# impulse.net
KiCad netlist of a schematic drawn in EAGLE
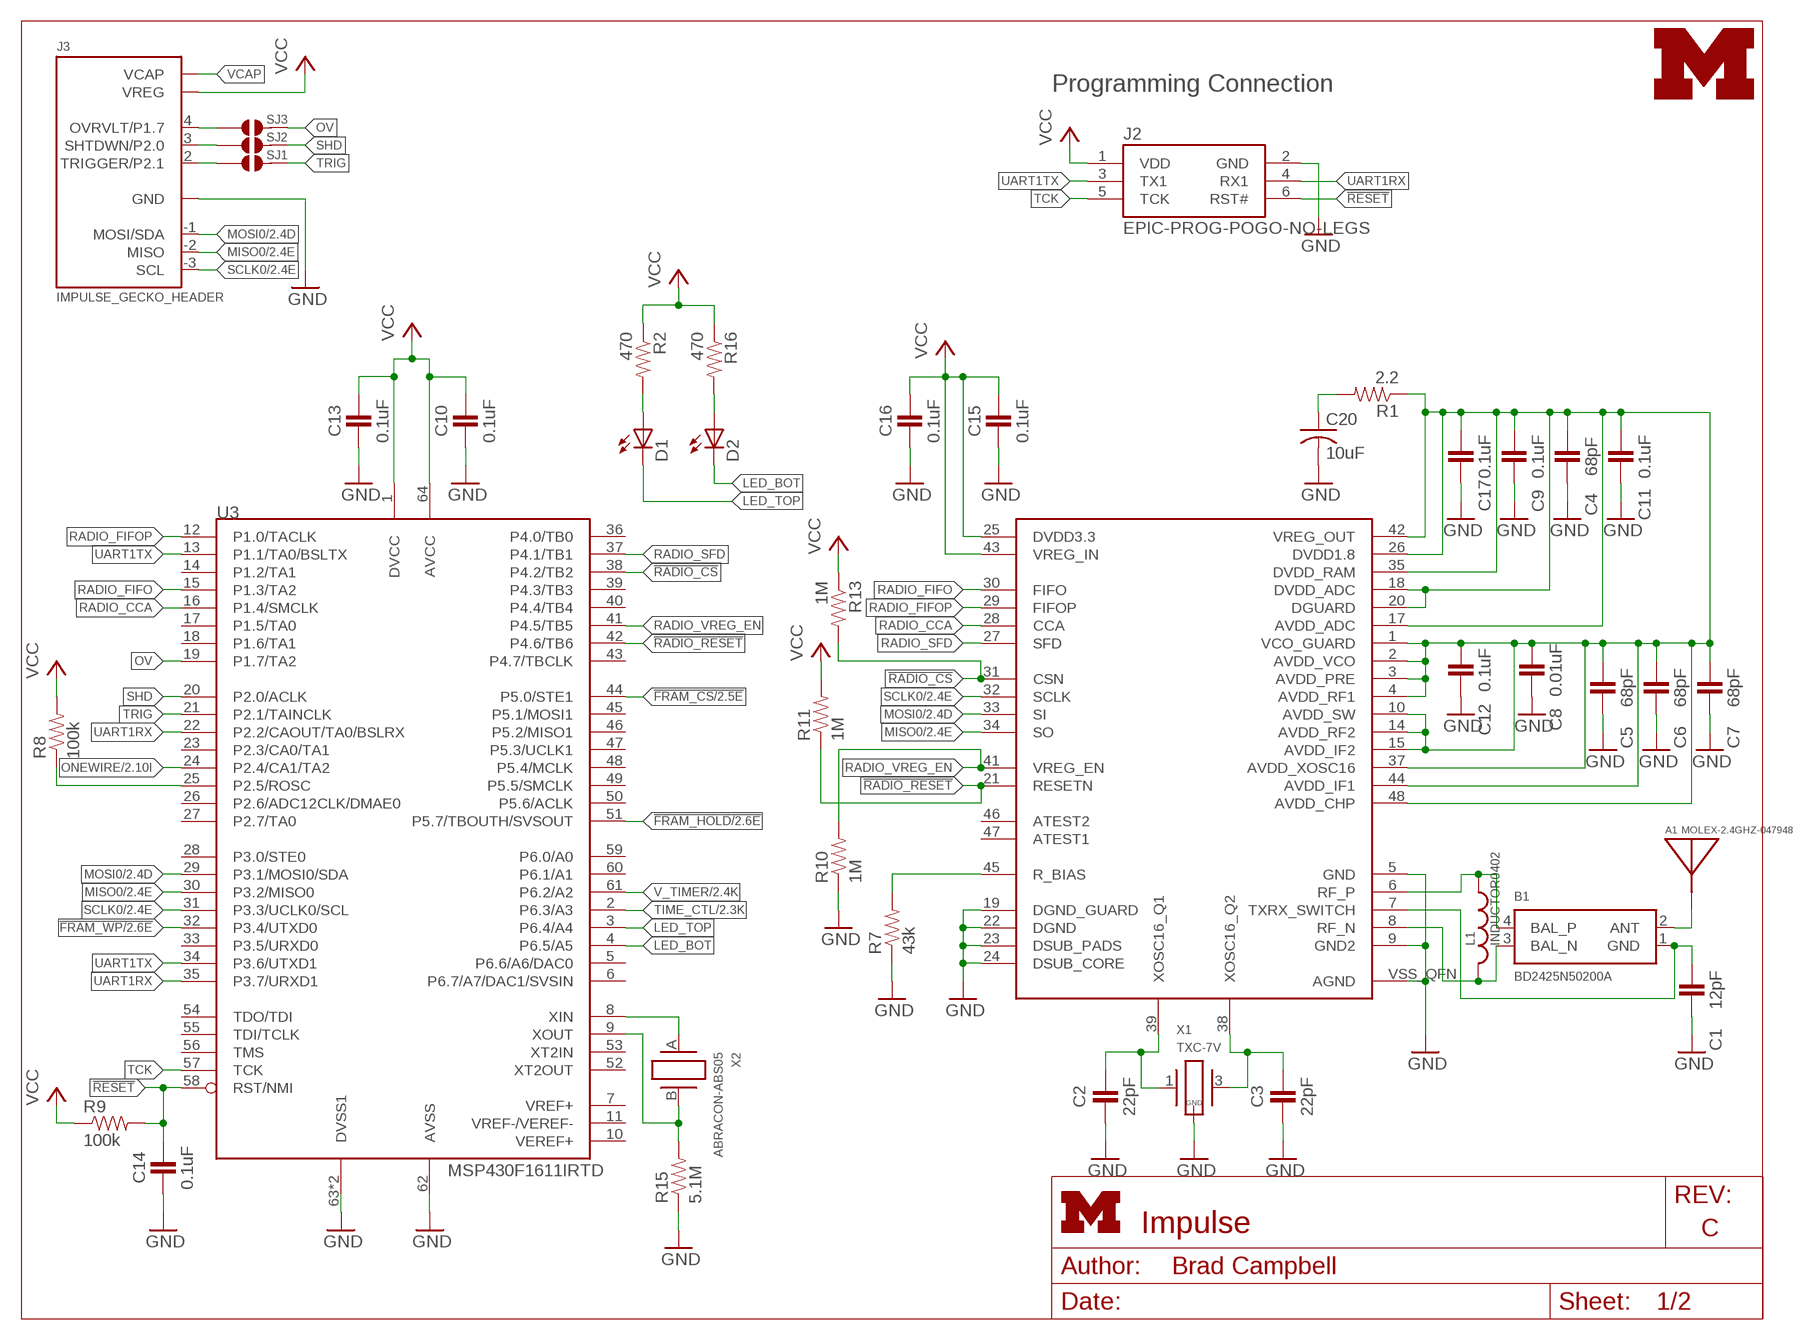
[diagram p0: schematic, sheet 1]
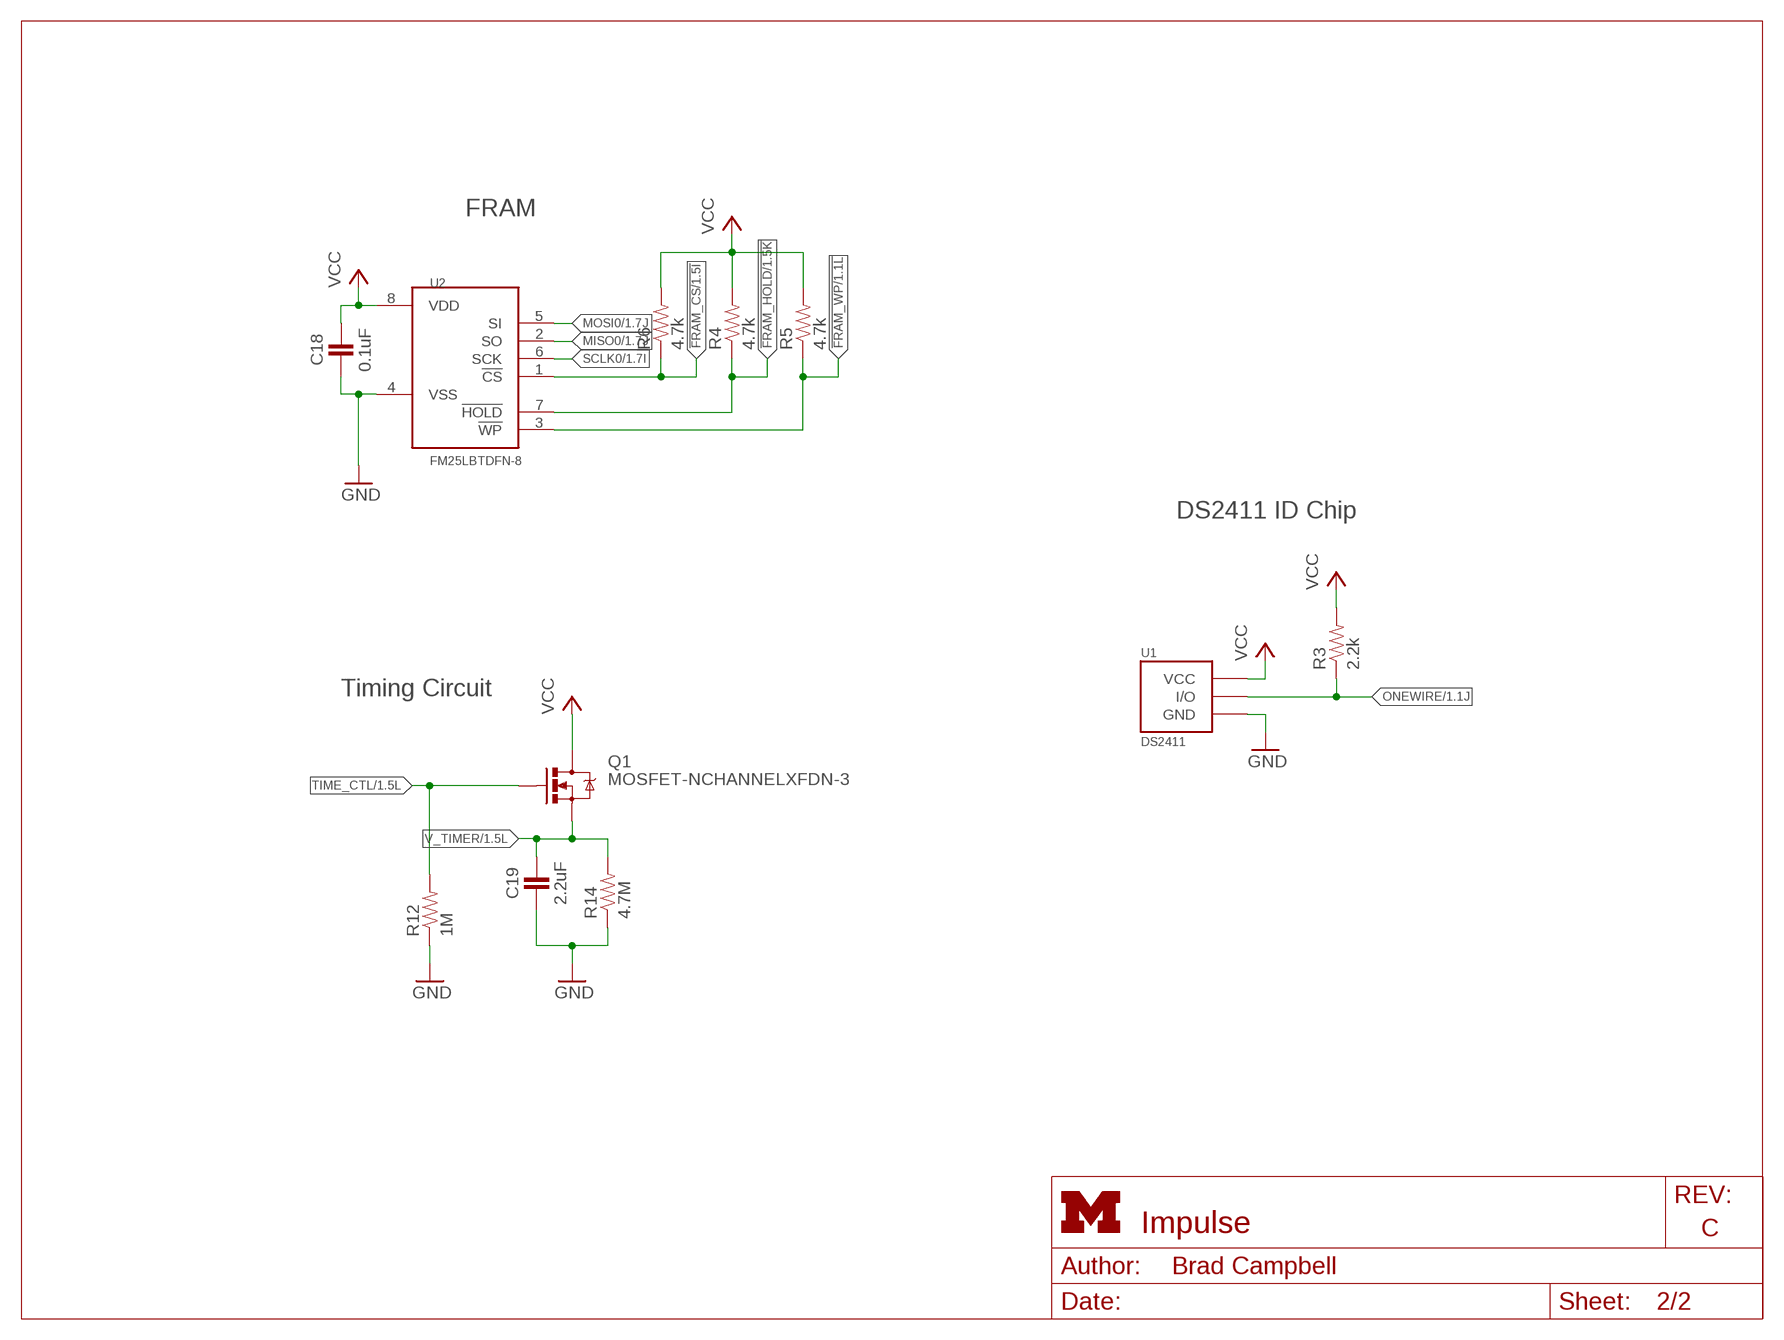
[diagram p1: schematic, sheet 2]

(export (version "E")
  (design (tool "Eeschema 10.0.6"))
  (components
    (comp (ref "C18")
      (value "0.1uF")
      (footprint "eagle-import:0402_CAP")
      (libsource (lib "eagle-import") (part "CAPACITOR"))
    )
    (comp (ref "C19")
      (value "2.2uF")
      (footprint "eagle-import:0402_CAP")
      (libsource (lib "eagle-import") (part "CAPACITOR"))
    )
    (comp (ref "Q1")
      (value "MOSFET-NCHANNELXFDN-3")
      (footprint "eagle-import:XFDFN-3")
      (libsource (lib "eagle-import") (part "MOSFET-NCHANNELXFDN-3"))
    )
    (comp (ref "R3")
      (value "2.2k")
      (footprint "eagle-import:0402_RES")
      (libsource (lib "eagle-import") (part "RESISTOR"))
    )
    (comp (ref "R4")
      (value "4.7k")
      (footprint "eagle-import:0402_RES")
      (libsource (lib "eagle-import") (part "RESISTOR"))
    )
    (comp (ref "R5")
      (value "4.7k")
      (footprint "eagle-import:0402_RES")
      (libsource (lib "eagle-import") (part "RESISTOR"))
    )
    (comp (ref "R6")
      (value "4.7k")
      (footprint "eagle-import:0402_RES")
      (libsource (lib "eagle-import") (part "RESISTOR"))
    )
    (comp (ref "R12")
      (value "1M")
      (footprint "eagle-import:0402_RES")
      (libsource (lib "eagle-import") (part "RESISTOR"))
    )
    (comp (ref "R14")
      (value "4.7M")
      (footprint "eagle-import:0402_RES")
      (libsource (lib "eagle-import") (part "RESISTOR"))
    )
    (comp (ref "U1")
      (value "DS2411")
      (footprint "eagle-import:SOT-23")
      (libsource (lib "eagle-import") (part "DS2411"))
    )
    (comp (ref "U2")
      (value "FM25LBTDFN-8")
      (footprint "eagle-import:TDFN-8")
      (libsource (lib "eagle-import") (part "FM25LBTDFN-8"))
    )
    (comp (ref "A1")
      (value "MOLEX-2.4GHZ-047948")
      (footprint "eagle-import:MOLEX-47948-ANTENNA")
      (libsource (lib "eagle-import") (part "MOLEX-2.4GHZ-047948"))
    )
    (comp (ref "B1")
      (value "BD2425N50200A")
      (footprint "eagle-import:BD2425N50200A")
      (libsource (lib "eagle-import") (part "BD2425N50200A"))
    )
    (comp (ref "C1")
      (value "12pF")
      (footprint "eagle-import:0402_CAP")
      (libsource (lib "eagle-import") (part "CAPACITOR"))
    )
    (comp (ref "C2")
      (value "22pF")
      (footprint "eagle-import:0402_CAP")
      (libsource (lib "eagle-import") (part "CAPACITOR"))
    )
    (comp (ref "C3")
      (value "22pF")
      (footprint "eagle-import:0402_CAP")
      (libsource (lib "eagle-import") (part "CAPACITOR"))
    )
    (comp (ref "C4")
      (value "68pF")
      (footprint "eagle-import:0402_CAP")
      (libsource (lib "eagle-import") (part "CAPACITOR"))
    )
    (comp (ref "C5")
      (value "68pF")
      (footprint "eagle-import:0402_CAP")
      (libsource (lib "eagle-import") (part "CAPACITOR"))
    )
    (comp (ref "C6")
      (value "68pF")
      (footprint "eagle-import:0402_CAP")
      (libsource (lib "eagle-import") (part "CAPACITOR"))
    )
    (comp (ref "C7")
      (value "68pF")
      (footprint "eagle-import:0402_CAP")
      (libsource (lib "eagle-import") (part "CAPACITOR"))
    )
    (comp (ref "C8")
      (value "0.01uF")
      (footprint "eagle-import:0402_CAP")
      (libsource (lib "eagle-import") (part "CAPACITOR"))
    )
    (comp (ref "C9")
      (value "0.1uF")
      (footprint "eagle-import:0402_CAP")
      (libsource (lib "eagle-import") (part "CAPACITOR"))
    )
    (comp (ref "C10")
      (value "0.1uF")
      (footprint "eagle-import:0402_CAP")
      (libsource (lib "eagle-import") (part "CAPACITOR"))
    )
    (comp (ref "C11")
      (value "0.1uF")
      (footprint "eagle-import:0402_CAP")
      (libsource (lib "eagle-import") (part "CAPACITOR"))
    )
    (comp (ref "C12")
      (value "0.1uF")
      (footprint "eagle-import:0402_CAP")
      (libsource (lib "eagle-import") (part "CAPACITOR"))
    )
    (comp (ref "C13")
      (value "0.1uF")
      (footprint "eagle-import:0402_CAP")
      (libsource (lib "eagle-import") (part "CAPACITOR"))
    )
    (comp (ref "C14")
      (value "0.1uF")
      (footprint "eagle-import:0402_CAP")
      (libsource (lib "eagle-import") (part "CAPACITOR"))
    )
    (comp (ref "C15")
      (value "0.1uF")
      (footprint "eagle-import:0402_CAP")
      (libsource (lib "eagle-import") (part "CAPACITOR"))
    )
    (comp (ref "C16")
      (value "0.1uF")
      (footprint "eagle-import:0402_CAP")
      (libsource (lib "eagle-import") (part "CAPACITOR"))
    )
    (comp (ref "C17")
      (value "0.1uF")
      (footprint "eagle-import:0402_CAP")
      (libsource (lib "eagle-import") (part "CAPACITOR"))
    )
    (comp (ref "C20")
      (value "10uF")
      (footprint "eagle-import:C0805")
      (libsource (lib "eagle-import") (part "C-USC0805"))
    )
    (comp (ref "D1")
      (value "LED0603")
      (footprint "eagle-import:LED-0603")
      (libsource (lib "eagle-import") (part "LED0603"))
    )
    (comp (ref "D2")
      (value "LED0603")
      (footprint "eagle-import:LED-0603")
      (libsource (lib "eagle-import") (part "LED0603"))
    )
    (comp (ref "J2")
      (value "EPIC-PROG-POGO-NO-LEGS")
      (footprint "eagle-import:TC2030-IDC-NL")
      (libsource (lib "eagle-import") (part "EPIC-PROG-POGO-NO-LEGS"))
    )
    (comp (ref "J3")
      (value "IMPULSE_GECKO_HEADER")
      (footprint "eagle-import:HEADER1X9_0.05IN")
      (libsource (lib "eagle-import") (part "IMPULSE_GECKO_HEADER"))
    )
    (comp (ref "L1")
      (value "INDUCTOR0402")
      (footprint "eagle-import:0402_CAP")
      (libsource (lib "eagle-import") (part "INDUCTOR0402"))
    )
    (comp (ref "R1")
      (value "2.2")
      (footprint "eagle-import:0402_RES")
      (libsource (lib "eagle-import") (part "RESISTOR"))
    )
    (comp (ref "R2")
      (value "470")
      (footprint "eagle-import:0402_RES")
      (libsource (lib "eagle-import") (part "RESISTOR"))
    )
    (comp (ref "R7")
      (value "43k")
      (footprint "eagle-import:0402_RES")
      (libsource (lib "eagle-import") (part "RESISTOR"))
    )
    (comp (ref "R8")
      (value "100k")
      (footprint "eagle-import:0402_RES")
      (libsource (lib "eagle-import") (part "RESISTOR"))
    )
    (comp (ref "R9")
      (value "100k")
      (footprint "eagle-import:0402_RES")
      (libsource (lib "eagle-import") (part "RESISTOR"))
    )
    (comp (ref "R10")
      (value "1M")
      (footprint "eagle-import:0402_RES")
      (libsource (lib "eagle-import") (part "RESISTOR"))
    )
    (comp (ref "R11")
      (value "1M")
      (footprint "eagle-import:0402_RES")
      (libsource (lib "eagle-import") (part "RESISTOR"))
    )
    (comp (ref "R13")
      (value "1M")
      (footprint "eagle-import:0402_RES")
      (libsource (lib "eagle-import") (part "RESISTOR"))
    )
    (comp (ref "R15")
      (value "5.1M")
      (footprint "eagle-import:0402_RES")
      (libsource (lib "eagle-import") (part "RESISTOR"))
    )
    (comp (ref "R16")
      (value "470")
      (footprint "eagle-import:0402_RES")
      (libsource (lib "eagle-import") (part "RESISTOR"))
    )
    (comp (ref "SJ1")
      (value "SJ")
      (footprint "eagle-import:SJ-0202")
      (libsource (lib "eagle-import") (part "SJ"))
    )
    (comp (ref "SJ2")
      (value "SJ")
      (footprint "eagle-import:SJ-0202")
      (libsource (lib "eagle-import") (part "SJ"))
    )
    (comp (ref "SJ3")
      (value "SJ")
      (footprint "eagle-import:SJ-0202")
      (libsource (lib "eagle-import") (part "SJ"))
    )
    (comp (ref "U$1")
      (value "UMICH_SOLID_SMALL")
      (footprint "eagle-import:UMICH_SOLID_75MIL")
      (libsource (lib "eagle-import") (part "UMICH_SOLID_SMALL"))
    )
    (comp (ref "U3")
      (value "MSP430F1611IRTD")
      (footprint "eagle-import:S-PVQFN-N64")
      (libsource (lib "eagle-import") (part "MSP430F1611IRTD"))
    )
    (comp (ref "U4")
      (value "CC2420RGZ")
      (footprint "eagle-import:S-PVQFN-N48")
      (libsource (lib "eagle-import") (part "CC2420RGZ"))
    )
    (comp (ref "X1")
      (value "TXC-7V")
      (footprint "eagle-import:TXC-7V")
      (libsource (lib "eagle-import") (part "TXC-7V"))
    )
    (comp (ref "X2")
      (value "ABRACON-ABS05")
      (footprint "eagle-import:ABS05")
      (libsource (lib "eagle-import") (part "ABRACON-ABS05"))
    )
  )
  (nets
    (net (code "1") (name "GND") (class "Default")
      (node (ref "C1") (pin "2") (pinfunction "2_2") (pintype "bidirectional"))
      (node (ref "C10") (pin "2") (pinfunction "2_2") (pintype "bidirectional"))
      (node (ref "C11") (pin "2") (pinfunction "2_2") (pintype "bidirectional"))
      (node (ref "C12") (pin "2") (pinfunction "2_2") (pintype "bidirectional"))
      (node (ref "C13") (pin "2") (pinfunction "2_2") (pintype "bidirectional"))
      (node (ref "C14") (pin "2") (pinfunction "2_2") (pintype "bidirectional"))
      (node (ref "C15") (pin "2") (pinfunction "2_2") (pintype "bidirectional"))
      (node (ref "C16") (pin "2") (pinfunction "2_2") (pintype "bidirectional"))
      (node (ref "C17") (pin "2") (pinfunction "2_2") (pintype "bidirectional"))
      (node (ref "C18") (pin "2") (pinfunction "2_2") (pintype "bidirectional"))
      (node (ref "C19") (pin "2") (pinfunction "2_2") (pintype "bidirectional"))
      (node (ref "C2") (pin "2") (pinfunction "2_2") (pintype "bidirectional"))
      (node (ref "C20") (pin "2") (pinfunction "2_2") (pintype "passive"))
      (node (ref "C3") (pin "2") (pinfunction "2_2") (pintype "bidirectional"))
      (node (ref "C4") (pin "2") (pinfunction "2_2") (pintype "bidirectional"))
      (node (ref "C5") (pin "2") (pinfunction "2_2") (pintype "bidirectional"))
      (node (ref "C6") (pin "2") (pinfunction "2_2") (pintype "bidirectional"))
      (node (ref "C7") (pin "2") (pinfunction "2_2") (pintype "bidirectional"))
      (node (ref "C8") (pin "2") (pinfunction "2_2") (pintype "bidirectional"))
      (node (ref "C9") (pin "2") (pinfunction "2_2") (pintype "bidirectional"))
      (node (ref "J2") (pin "2") (pinfunction "GND_2") (pintype "bidirectional"))
      (node (ref "J3") (pin "0") (pinfunction "GND_0") (pintype "bidirectional"))
      (node (ref "R10") (pin "1") (pinfunction "1_1") (pintype "passive"))
      (node (ref "R12") (pin "1") (pinfunction "1_1") (pintype "passive"))
      (node (ref "R14") (pin "1") (pinfunction "1_1") (pintype "passive"))
      (node (ref "R15") (pin "1") (pinfunction "1_1") (pintype "passive"))
      (node (ref "R7") (pin "1") (pinfunction "1_1") (pintype "passive"))
      (node (ref "U1") (pin "3") (pinfunction "GND_3") (pintype "bidirectional"))
      (node (ref "U2") (pin "4") (pinfunction "VSS_4") (pintype "bidirectional"))
      (node (ref "U3") (pin "62") (pinfunction "AVSS_62") (pintype "power_in"))
      (node (ref "U3") (pin "63") (pinfunction "DVSS1_63") (pintype "power_in"))
      (node (ref "U3") (pin "GND") (pinfunction "DVSS1_GND") (pintype "power_in"))
      (node (ref "U4") (pin "19") (pinfunction "DGND_GUARD_19") (pintype "bidirectional"))
      (node (ref "U4") (pin "22") (pinfunction "DGND_22") (pintype "bidirectional"))
      (node (ref "U4") (pin "23") (pinfunction "DSUB_PADS_23") (pintype "bidirectional"))
      (node (ref "U4") (pin "24") (pinfunction "DSUB_CORE_24") (pintype "bidirectional"))
      (node (ref "U4") (pin "5") (pinfunction "GND_5") (pintype "bidirectional"))
      (node (ref "U4") (pin "9") (pinfunction "GND2_9") (pintype "bidirectional"))
      (node (ref "U4") (pin "VSS_QFN") (pinfunction "AGND_VSS_QFN") (pintype "bidirectional"))
      (node (ref "X1") (pin "2") (pinfunction "GND_2") (pintype "bidirectional"))
      (node (ref "X1") (pin "4") (pinfunction "GND_4") (pintype "bidirectional"))
    )
    (net (code "2") (name "LED_BOT") (class "Default")
      (node (ref "D2") (pin "C") (pinfunction "C_C") (pintype "passive"))
      (node (ref "U3") (pin "4") (pinfunction "P6.5/A5_4") (pintype "bidirectional"))
    )
    (net (code "3") (name "LED_TOP") (class "Default")
      (node (ref "D1") (pin "C") (pinfunction "C_C") (pintype "passive"))
      (node (ref "U3") (pin "3") (pinfunction "P6.4/A4_3") (pintype "bidirectional"))
    )
    (net (code "4") (name "MISO0") (class "Default")
      (node (ref "J3") (pin "-2") (pinfunction "MISO_-2") (pintype "bidirectional"))
      (node (ref "U2") (pin "2") (pinfunction "SO_2") (pintype "bidirectional"))
      (node (ref "U3") (pin "30") (pinfunction "P3.2/MISO0_30") (pintype "bidirectional"))
      (node (ref "U4") (pin "34") (pinfunction "SO_34") (pintype "bidirectional"))
    )
    (net (code "5") (name "MOSI0") (class "Default")
      (node (ref "J3") (pin "-1") (pinfunction "MOSI/SDA_-1") (pintype "bidirectional"))
      (node (ref "U2") (pin "5") (pinfunction "SI_5") (pintype "bidirectional"))
      (node (ref "U3") (pin "29") (pinfunction "P3.1/MOSI0/SDA_29") (pintype "bidirectional"))
      (node (ref "U4") (pin "33") (pinfunction "SI_33") (pintype "bidirectional"))
    )
    (net (code "6") (name "Net-(A1-ANTENNA)") (class "Default")
      (node (ref "A1") (pin "1") (pinfunction "ANTENNA_1") (pintype "bidirectional"))
      (node (ref "B1") (pin "2") (pinfunction "ANT_2") (pintype "bidirectional"))
    )
    (net (code "7") (name "Net-(B1-BAL_N)") (class "Default")
      (node (ref "B1") (pin "3") (pinfunction "BAL_N_3") (pintype "bidirectional"))
      (node (ref "L1") (pin "2") (pinfunction "P$2_2") (pintype "bidirectional"))
      (node (ref "U4") (pin "8") (pinfunction "RF_N_8") (pintype "bidirectional"))
    )
    (net (code "8") (name "Net-(B1-BAL_P)") (class "Default")
      (node (ref "B1") (pin "4") (pinfunction "BAL_P_4") (pintype "bidirectional"))
      (node (ref "L1") (pin "1") (pinfunction "1_1") (pintype "bidirectional"))
      (node (ref "U4") (pin "6") (pinfunction "RF_P_6") (pintype "bidirectional"))
    )
    (net (code "9") (name "Net-(B1-GND)") (class "Default")
      (node (ref "B1") (pin "1") (pinfunction "GND_1") (pintype "bidirectional"))
      (node (ref "C1") (pin "1") (pinfunction "1_1") (pintype "bidirectional"))
      (node (ref "U4") (pin "7") (pinfunction "TXRX_SWITCH_7") (pintype "bidirectional"))
    )
    (net (code "10") (name "Net-(C20-Pad1)") (class "Default")
      (node (ref "C20") (pin "1") (pinfunction "1_1") (pintype "passive"))
      (node (ref "R1") (pin "2") (pinfunction "2_2") (pintype "passive"))
    )
    (net (code "11") (name "Net-(D1-PadA)") (class "Default")
      (node (ref "D1") (pin "A") (pinfunction "A_A") (pintype "passive"))
      (node (ref "R2") (pin "2") (pinfunction "2_2") (pintype "passive"))
    )
    (net (code "12") (name "Net-(D2-PadA)") (class "Default")
      (node (ref "D2") (pin "A") (pinfunction "A_A") (pintype "passive"))
      (node (ref "R16") (pin "2") (pinfunction "2_2") (pintype "passive"))
    )
    (net (code "13") (name "Net-(J3-OVRVLT{slash}P1.7)") (class "Default")
      (node (ref "J3") (pin "4") (pinfunction "OVRVLT/P1.7_4") (pintype "bidirectional"))
      (node (ref "SJ3") (pin "1") (pinfunction "P$1_1") (pintype "bidirectional"))
    )
    (net (code "14") (name "Net-(J3-SHTDWN{slash}P2.0)") (class "Default")
      (node (ref "J3") (pin "3") (pinfunction "SHTDWN/P2.0_3") (pintype "bidirectional"))
      (node (ref "SJ2") (pin "1") (pinfunction "P$1_1") (pintype "bidirectional"))
    )
    (net (code "15") (name "Net-(J3-TRIGGER{slash}P2.1)") (class "Default")
      (node (ref "J3") (pin "2") (pinfunction "TRIGGER/P2.1_2") (pintype "bidirectional"))
      (node (ref "SJ1") (pin "1") (pinfunction "P$1_1") (pintype "bidirectional"))
    )
    (net (code "16") (name "Net-(U3-P2.5{slash}ROSC)") (class "Default")
      (node (ref "R8") (pin "1") (pinfunction "1_1") (pintype "passive"))
      (node (ref "U3") (pin "25") (pinfunction "P2.5/ROSC_25") (pintype "bidirectional"))
    )
    (net (code "17") (name "Net-(U3-XIN)") (class "Default")
      (node (ref "U3") (pin "8") (pinfunction "XIN_8") (pintype "bidirectional"))
      (node (ref "X2") (pin "A") (pinfunction "1_A") (pintype "bidirectional"))
    )
    (net (code "18") (name "Net-(U3-XOUT)") (class "Default")
      (node (ref "R15") (pin "2") (pinfunction "2_2") (pintype "passive"))
      (node (ref "U3") (pin "9") (pinfunction "XOUT_9") (pintype "bidirectional"))
      (node (ref "X2") (pin "B") (pinfunction "2_B") (pintype "bidirectional"))
    )
    (net (code "19") (name "Net-(U4-AVDD_ADC)") (class "Default")
      (node (ref "C11") (pin "1") (pinfunction "1_1") (pintype "bidirectional"))
      (node (ref "C12") (pin "1") (pinfunction "1_1") (pintype "bidirectional"))
      (node (ref "C17") (pin "1") (pinfunction "1_1") (pintype "bidirectional"))
      (node (ref "C4") (pin "1") (pinfunction "1_1") (pintype "bidirectional"))
      (node (ref "C5") (pin "1") (pinfunction "1_1") (pintype "bidirectional"))
      (node (ref "C6") (pin "1") (pinfunction "1_1") (pintype "bidirectional"))
      (node (ref "C7") (pin "1") (pinfunction "1_1") (pintype "bidirectional"))
      (node (ref "C8") (pin "1") (pinfunction "1_1") (pintype "bidirectional"))
      (node (ref "C9") (pin "1") (pinfunction "1_1") (pintype "bidirectional"))
      (node (ref "R1") (pin "1") (pinfunction "1_1") (pintype "passive"))
      (node (ref "U4") (pin "1") (pinfunction "VCO_GUARD_1") (pintype "bidirectional"))
      (node (ref "U4") (pin "10") (pinfunction "AVDD_SW_10") (pintype "bidirectional"))
      (node (ref "U4") (pin "14") (pinfunction "AVDD_RF2_14") (pintype "bidirectional"))
      (node (ref "U4") (pin "15") (pinfunction "AVDD_IF2_15") (pintype "bidirectional"))
      (node (ref "U4") (pin "17") (pinfunction "AVDD_ADC_17") (pintype "bidirectional"))
      (node (ref "U4") (pin "18") (pinfunction "DVDD_ADC_18") (pintype "bidirectional"))
      (node (ref "U4") (pin "2") (pinfunction "AVDD_VCO_2") (pintype "bidirectional"))
      (node (ref "U4") (pin "20") (pinfunction "DGUARD_20") (pintype "bidirectional"))
      (node (ref "U4") (pin "26") (pinfunction "DVDD1.8_26") (pintype "bidirectional"))
      (node (ref "U4") (pin "3") (pinfunction "AVDD_PRE_3") (pintype "bidirectional"))
      (node (ref "U4") (pin "35") (pinfunction "DVDD_RAM_35") (pintype "bidirectional"))
      (node (ref "U4") (pin "37") (pinfunction "AVDD_XOSC16_37") (pintype "bidirectional"))
      (node (ref "U4") (pin "4") (pinfunction "AVDD_RF1_4") (pintype "bidirectional"))
      (node (ref "U4") (pin "42") (pinfunction "VREG_OUT_42") (pintype "bidirectional"))
      (node (ref "U4") (pin "44") (pinfunction "AVDD_IF1_44") (pintype "bidirectional"))
      (node (ref "U4") (pin "48") (pinfunction "AVDD_CHP_48") (pintype "bidirectional"))
    )
    (net (code "20") (name "Net-(U4-R_BIAS)") (class "Default")
      (node (ref "R7") (pin "2") (pinfunction "2_2") (pintype "passive"))
      (node (ref "U4") (pin "45") (pinfunction "R_BIAS_45") (pintype "bidirectional"))
    )
    (net (code "21") (name "Net-(U4-XOSC16_Q1)") (class "Default")
      (node (ref "C2") (pin "1") (pinfunction "1_1") (pintype "bidirectional"))
      (node (ref "U4") (pin "39") (pinfunction "XOSC16_Q1_39") (pintype "bidirectional"))
      (node (ref "X1") (pin "1") (pinfunction "1_1") (pintype "bidirectional"))
    )
    (net (code "22") (name "Net-(U4-XOSC16_Q2)") (class "Default")
      (node (ref "C3") (pin "1") (pinfunction "1_1") (pintype "bidirectional"))
      (node (ref "U4") (pin "38") (pinfunction "XOSC16_Q2_38") (pintype "bidirectional"))
      (node (ref "X1") (pin "3") (pinfunction "2_3") (pintype "bidirectional"))
    )
    (net (code "23") (name "ONEWIRE") (class "Default")
      (node (ref "R3") (pin "1") (pinfunction "1_1") (pintype "passive"))
      (node (ref "U1") (pin "1") (pinfunction "I/O_1") (pintype "bidirectional"))
      (node (ref "U3") (pin "24") (pinfunction "P2.4/CA1/TA2_24") (pintype "bidirectional"))
    )
    (net (code "24") (name "OV") (class "Default")
      (node (ref "SJ3") (pin "2") (pinfunction "P$2_2") (pintype "bidirectional"))
      (node (ref "U3") (pin "19") (pinfunction "P1.7/TA2_19") (pintype "bidirectional"))
    )
    (net (code "25") (name "RADIO_CCA") (class "Default")
      (node (ref "U3") (pin "16") (pinfunction "P1.4/SMCLK_16") (pintype "bidirectional"))
      (node (ref "U4") (pin "28") (pinfunction "CCA_28") (pintype "bidirectional"))
    )
    (net (code "26") (name "RADIO_FIFO") (class "Default")
      (node (ref "U3") (pin "15") (pinfunction "P1.3/TA2_15") (pintype "bidirectional"))
      (node (ref "U4") (pin "30") (pinfunction "FIFO_30") (pintype "bidirectional"))
    )
    (net (code "27") (name "RADIO_FIFOP") (class "Default")
      (node (ref "U3") (pin "12") (pinfunction "P1.0/TACLK_12") (pintype "bidirectional"))
      (node (ref "U4") (pin "29") (pinfunction "FIFOP_29") (pintype "bidirectional"))
    )
    (net (code "28") (name "RADIO_SFD") (class "Default")
      (node (ref "U3") (pin "37") (pinfunction "P4.1/TB1_37") (pintype "bidirectional"))
      (node (ref "U4") (pin "27") (pinfunction "SFD_27") (pintype "bidirectional"))
    )
    (net (code "29") (name "RADIO_VREG_EN") (class "Default")
      (node (ref "R10") (pin "2") (pinfunction "2_2") (pintype "passive"))
      (node (ref "U3") (pin "41") (pinfunction "P4.5/TB5_41") (pintype "bidirectional"))
      (node (ref "U4") (pin "41") (pinfunction "VREG_EN_41") (pintype "bidirectional"))
    )
    (net (code "30") (name "SCLK0") (class "Default")
      (node (ref "J3") (pin "-3") (pinfunction "SCL_-3") (pintype "bidirectional"))
      (node (ref "U2") (pin "6") (pinfunction "SCK_6") (pintype "bidirectional"))
      (node (ref "U3") (pin "31") (pinfunction "P3.3/UCLK0/SCL_31") (pintype "bidirectional"))
      (node (ref "U4") (pin "32") (pinfunction "SCLK_32") (pintype "bidirectional"))
    )
    (net (code "31") (name "SHD") (class "Default")
      (node (ref "SJ2") (pin "2") (pinfunction "P$2_2") (pintype "bidirectional"))
      (node (ref "U3") (pin "20") (pinfunction "P2.0/ACLK_20") (pintype "bidirectional"))
    )
    (net (code "32") (name "TCK") (class "Default")
      (node (ref "J2") (pin "5") (pinfunction "TCK_5") (pintype "bidirectional"))
      (node (ref "U3") (pin "57") (pinfunction "TCK_57") (pintype "bidirectional"))
    )
    (net (code "33") (name "TIME_CTL") (class "Default")
      (node (ref "Q1") (pin "G") (pinfunction "G_G") (pintype "passive"))
      (node (ref "R12") (pin "2") (pinfunction "2_2") (pintype "passive"))
      (node (ref "U3") (pin "2") (pinfunction "P6.3/A3_2") (pintype "bidirectional"))
    )
    (net (code "34") (name "TRIG") (class "Default")
      (node (ref "SJ1") (pin "2") (pinfunction "P$2_2") (pintype "bidirectional"))
      (node (ref "U3") (pin "21") (pinfunction "P2.1/TAINCLK_21") (pintype "bidirectional"))
    )
    (net (code "35") (name "UART1RX") (class "Default")
      (node (ref "J2") (pin "4") (pinfunction "RX1_4") (pintype "bidirectional"))
      (node (ref "U3") (pin "22") (pinfunction "P2.2/CAOUT/TA0/BSLRX_22") (pintype "bidirectional"))
      (node (ref "U3") (pin "35") (pinfunction "P3.7/URXD1_35") (pintype "bidirectional"))
    )
    (net (code "36") (name "UART1TX") (class "Default")
      (node (ref "J2") (pin "3") (pinfunction "TX1_3") (pintype "bidirectional"))
      (node (ref "U3") (pin "13") (pinfunction "P1.1/TA0/BSLTX_13") (pintype "bidirectional"))
      (node (ref "U3") (pin "34") (pinfunction "P3.6/UTXD1_34") (pintype "bidirectional"))
    )
    (net (code "37") (name "VCAP") (class "Default")
      (node (ref "J3") (pin "5") (pinfunction "VCAP_5") (pintype "output"))
    )
    (net (code "38") (name "VCC") (class "Default")
      (node (ref "C10") (pin "1") (pinfunction "1_1") (pintype "bidirectional"))
      (node (ref "C13") (pin "1") (pinfunction "1_1") (pintype "bidirectional"))
      (node (ref "C15") (pin "1") (pinfunction "1_1") (pintype "bidirectional"))
      (node (ref "C16") (pin "1") (pinfunction "1_1") (pintype "bidirectional"))
      (node (ref "C18") (pin "1") (pinfunction "1_1") (pintype "bidirectional"))
      (node (ref "J2") (pin "1") (pinfunction "VDD_1") (pintype "bidirectional"))
      (node (ref "J3") (pin "1") (pinfunction "VREG_1") (pintype "bidirectional"))
      (node (ref "Q1") (pin "D") (pinfunction "D_D") (pintype "passive"))
      (node (ref "R11") (pin "2") (pinfunction "2_2") (pintype "passive"))
      (node (ref "R13") (pin "1") (pinfunction "1_1") (pintype "passive"))
      (node (ref "R16") (pin "1") (pinfunction "1_1") (pintype "passive"))
      (node (ref "R2") (pin "1") (pinfunction "1_1") (pintype "passive"))
      (node (ref "R3") (pin "2") (pinfunction "2_2") (pintype "passive"))
      (node (ref "R4") (pin "2") (pinfunction "2_2") (pintype "passive"))
      (node (ref "R5") (pin "2") (pinfunction "2_2") (pintype "passive"))
      (node (ref "R6") (pin "2") (pinfunction "2_2") (pintype "passive"))
      (node (ref "R8") (pin "2") (pinfunction "2_2") (pintype "passive"))
      (node (ref "R9") (pin "1") (pinfunction "1_1") (pintype "passive"))
      (node (ref "U1") (pin "2") (pinfunction "VCC_2") (pintype "bidirectional"))
      (node (ref "U2") (pin "8") (pinfunction "VDD_8") (pintype "bidirectional"))
      (node (ref "U3") (pin "1") (pinfunction "DVCC_1") (pintype "power_in"))
      (node (ref "U3") (pin "64") (pinfunction "AVCC_64") (pintype "power_in"))
      (node (ref "U4") (pin "25") (pinfunction "DVDD3.3_25") (pintype "bidirectional"))
      (node (ref "U4") (pin "43") (pinfunction "VREG_IN_43") (pintype "bidirectional"))
    )
    (net (code "39") (name "V_TIMER") (class "Default")
      (node (ref "C19") (pin "1") (pinfunction "1_1") (pintype "bidirectional"))
      (node (ref "Q1") (pin "S") (pinfunction "S_S") (pintype "passive"))
      (node (ref "R14") (pin "2") (pinfunction "2_2") (pintype "passive"))
      (node (ref "U3") (pin "61") (pinfunction "P6.2/A2_61") (pintype "bidirectional"))
    )
    (net (code "40") (name "unconnected-(U3-P1.2{slash}TA1-Pad14)") (class "Default")
      (node (ref "U3") (pin "14") (pinfunction "P1.2/TA1_14") (pintype "bidirectional"))
    )
    (net (code "41") (name "unconnected-(U3-P1.5{slash}TA0-Pad17)") (class "Default")
      (node (ref "U3") (pin "17") (pinfunction "P1.5/TA0_17") (pintype "bidirectional"))
    )
    (net (code "42") (name "unconnected-(U3-P1.6{slash}TA1-Pad18)") (class "Default")
      (node (ref "U3") (pin "18") (pinfunction "P1.6/TA1_18") (pintype "bidirectional"))
    )
    (net (code "43") (name "unconnected-(U3-P2.3{slash}CA0{slash}TA1-Pad23)") (class "Default")
      (node (ref "U3") (pin "23") (pinfunction "P2.3/CA0/TA1_23") (pintype "bidirectional"))
    )
    (net (code "44") (name "unconnected-(U3-P2.6{slash}ADC12CLK{slash}DMAE0-Pad26)") (class "Default")
      (node (ref "U3") (pin "26") (pinfunction "P2.6/ADC12CLK/DMAE0_26") (pintype "bidirectional"))
    )
    (net (code "45") (name "unconnected-(U3-P2.7{slash}TA0-Pad27)") (class "Default")
      (node (ref "U3") (pin "27") (pinfunction "P2.7/TA0_27") (pintype "bidirectional"))
    )
    (net (code "46") (name "unconnected-(U3-P3.0{slash}STE0-Pad28)") (class "Default")
      (node (ref "U3") (pin "28") (pinfunction "P3.0/STE0_28") (pintype "bidirectional"))
    )
    (net (code "47") (name "unconnected-(U3-P3.5{slash}URXD0-Pad33)") (class "Default")
      (node (ref "U3") (pin "33") (pinfunction "P3.5/URXD0_33") (pintype "bidirectional"))
    )
    (net (code "48") (name "unconnected-(U3-P4.0{slash}TB0-Pad36)") (class "Default")
      (node (ref "U3") (pin "36") (pinfunction "P4.0/TB0_36") (pintype "bidirectional"))
    )
    (net (code "49") (name "unconnected-(U3-P4.3{slash}TB3-Pad39)") (class "Default")
      (node (ref "U3") (pin "39") (pinfunction "P4.3/TB3_39") (pintype "bidirectional"))
    )
    (net (code "50") (name "unconnected-(U3-P4.4{slash}TB4-Pad40)") (class "Default")
      (node (ref "U3") (pin "40") (pinfunction "P4.4/TB4_40") (pintype "bidirectional"))
    )
    (net (code "51") (name "unconnected-(U3-P4.7{slash}TBCLK-Pad43)") (class "Default")
      (node (ref "U3") (pin "43") (pinfunction "P4.7/TBCLK_43") (pintype "bidirectional"))
    )
    (net (code "52") (name "unconnected-(U3-P5.1{slash}MOSI1-Pad45)") (class "Default")
      (node (ref "U3") (pin "45") (pinfunction "P5.1/MOSI1_45") (pintype "bidirectional"))
    )
    (net (code "53") (name "unconnected-(U3-P5.2{slash}MISO1-Pad46)") (class "Default")
      (node (ref "U3") (pin "46") (pinfunction "P5.2/MISO1_46") (pintype "bidirectional"))
    )
    (net (code "54") (name "unconnected-(U3-P5.3{slash}UCLK1-Pad47)") (class "Default")
      (node (ref "U3") (pin "47") (pinfunction "P5.3/UCLK1_47") (pintype "bidirectional"))
    )
    (net (code "55") (name "unconnected-(U3-P5.4{slash}MCLK-Pad48)") (class "Default")
      (node (ref "U3") (pin "48") (pinfunction "P5.4/MCLK_48") (pintype "bidirectional"))
    )
    (net (code "56") (name "unconnected-(U3-P5.5{slash}SMCLK-Pad49)") (class "Default")
      (node (ref "U3") (pin "49") (pinfunction "P5.5/SMCLK_49") (pintype "bidirectional"))
    )
    (net (code "57") (name "unconnected-(U3-P5.6{slash}ACLK-Pad50)") (class "Default")
      (node (ref "U3") (pin "50") (pinfunction "P5.6/ACLK_50") (pintype "bidirectional"))
    )
    (net (code "58") (name "unconnected-(U3-P6.0{slash}A0-Pad59)") (class "Default")
      (node (ref "U3") (pin "59") (pinfunction "P6.0/A0_59") (pintype "bidirectional"))
    )
    (net (code "59") (name "unconnected-(U3-P6.1{slash}A1-Pad60)") (class "Default")
      (node (ref "U3") (pin "60") (pinfunction "P6.1/A1_60") (pintype "bidirectional"))
    )
    (net (code "60") (name "unconnected-(U3-P6.6{slash}A6{slash}DAC0-Pad5)") (class "Default")
      (node (ref "U3") (pin "5") (pinfunction "P6.6/A6/DAC0_5") (pintype "bidirectional"))
    )
    (net (code "61") (name "unconnected-(U3-P6.7{slash}A7{slash}DAC1{slash}SVSIN-Pad6)") (class "Default")
      (node (ref "U3") (pin "6") (pinfunction "P6.7/A7/DAC1/SVSIN_6") (pintype "bidirectional"))
    )
    (net (code "62") (name "unconnected-(U3-TDI{slash}TCLK-Pad55)") (class "Default")
      (node (ref "U3") (pin "55") (pinfunction "TDI/TCLK_55") (pintype "bidirectional"))
    )
    (net (code "63") (name "unconnected-(U3-TDO{slash}TDI-Pad54)") (class "Default")
      (node (ref "U3") (pin "54") (pinfunction "TDO/TDI_54") (pintype "bidirectional"))
    )
    (net (code "64") (name "unconnected-(U3-TMS-Pad56)") (class "Default")
      (node (ref "U3") (pin "56") (pinfunction "TMS_56") (pintype "bidirectional"))
    )
    (net (code "65") (name "unconnected-(U3-VEREF+-Pad10)") (class "Default")
      (node (ref "U3") (pin "10") (pinfunction "VEREF+_10") (pintype "bidirectional"))
    )
    (net (code "66") (name "unconnected-(U3-VREF+-Pad7)") (class "Default")
      (node (ref "U3") (pin "7") (pinfunction "VREF+_7") (pintype "bidirectional"))
    )
    (net (code "67") (name "unconnected-(U3-VREF-{slash}VEREF--Pad11)") (class "Default")
      (node (ref "U3") (pin "11") (pinfunction "VREF-/VEREF-_11") (pintype "bidirectional"))
    )
    (net (code "68") (name "unconnected-(U3-XT2IN-Pad53)") (class "Default")
      (node (ref "U3") (pin "53") (pinfunction "XT2IN_53") (pintype "bidirectional"))
    )
    (net (code "69") (name "unconnected-(U3-XT2OUT-Pad52)") (class "Default")
      (node (ref "U3") (pin "52") (pinfunction "XT2OUT_52") (pintype "bidirectional"))
    )
    (net (code "70") (name "unconnected-(U4-ATEST1-Pad47)") (class "Default")
      (node (ref "U4") (pin "47") (pinfunction "ATEST1_47") (pintype "bidirectional"))
    )
    (net (code "71") (name "unconnected-(U4-ATEST2-Pad46)") (class "Default")
      (node (ref "U4") (pin "46") (pinfunction "ATEST2_46") (pintype "bidirectional"))
    )
    (net (code "72") (name "~{FRAM_CS}") (class "Default")
      (node (ref "R6") (pin "1") (pinfunction "1_1") (pintype "passive"))
      (node (ref "U2") (pin "1") (pinfunction "~{CS}_1") (pintype "bidirectional"))
      (node (ref "U3") (pin "44") (pinfunction "P5.0/STE1_44") (pintype "bidirectional"))
    )
    (net (code "73") (name "~{FRAM_HOLD}") (class "Default")
      (node (ref "R4") (pin "1") (pinfunction "1_1") (pintype "passive"))
      (node (ref "U2") (pin "7") (pinfunction "~{HOLD}_7") (pintype "bidirectional"))
      (node (ref "U3") (pin "51") (pinfunction "P5.7/TBOUTH/SVSOUT_51") (pintype "bidirectional"))
    )
    (net (code "74") (name "~{FRAM_WP}") (class "Default")
      (node (ref "R5") (pin "1") (pinfunction "1_1") (pintype "passive"))
      (node (ref "U2") (pin "3") (pinfunction "~{WP}_3") (pintype "bidirectional"))
      (node (ref "U3") (pin "32") (pinfunction "P3.4/UTXD0_32") (pintype "bidirectional"))
    )
    (net (code "75") (name "~{RADIO_CS}") (class "Default")
      (node (ref "R13") (pin "2") (pinfunction "2_2") (pintype "passive"))
      (node (ref "U3") (pin "38") (pinfunction "P4.2/TB2_38") (pintype "bidirectional"))
      (node (ref "U4") (pin "31") (pinfunction "CSN_31") (pintype "bidirectional"))
    )
    (net (code "76") (name "~{RADIO_RESET}") (class "Default")
      (node (ref "R11") (pin "1") (pinfunction "1_1") (pintype "passive"))
      (node (ref "U3") (pin "42") (pinfunction "P4.6/TB6_42") (pintype "bidirectional"))
      (node (ref "U4") (pin "21") (pinfunction "RESETN_21") (pintype "bidirectional"))
    )
    (net (code "77") (name "~{RESET}") (class "Default")
      (node (ref "C14") (pin "1") (pinfunction "1_1") (pintype "bidirectional"))
      (node (ref "J2") (pin "6") (pinfunction "RST#_6") (pintype "bidirectional"))
      (node (ref "R9") (pin "2") (pinfunction "2_2") (pintype "passive"))
      (node (ref "U3") (pin "58") (pinfunction "RST/NMI_58") (pintype "bidirectional"))
    )
  )
)
